# SCH_michale_nfc_2023-10-15.net
KiCad netlist of a schematic drawn in EasyEDA
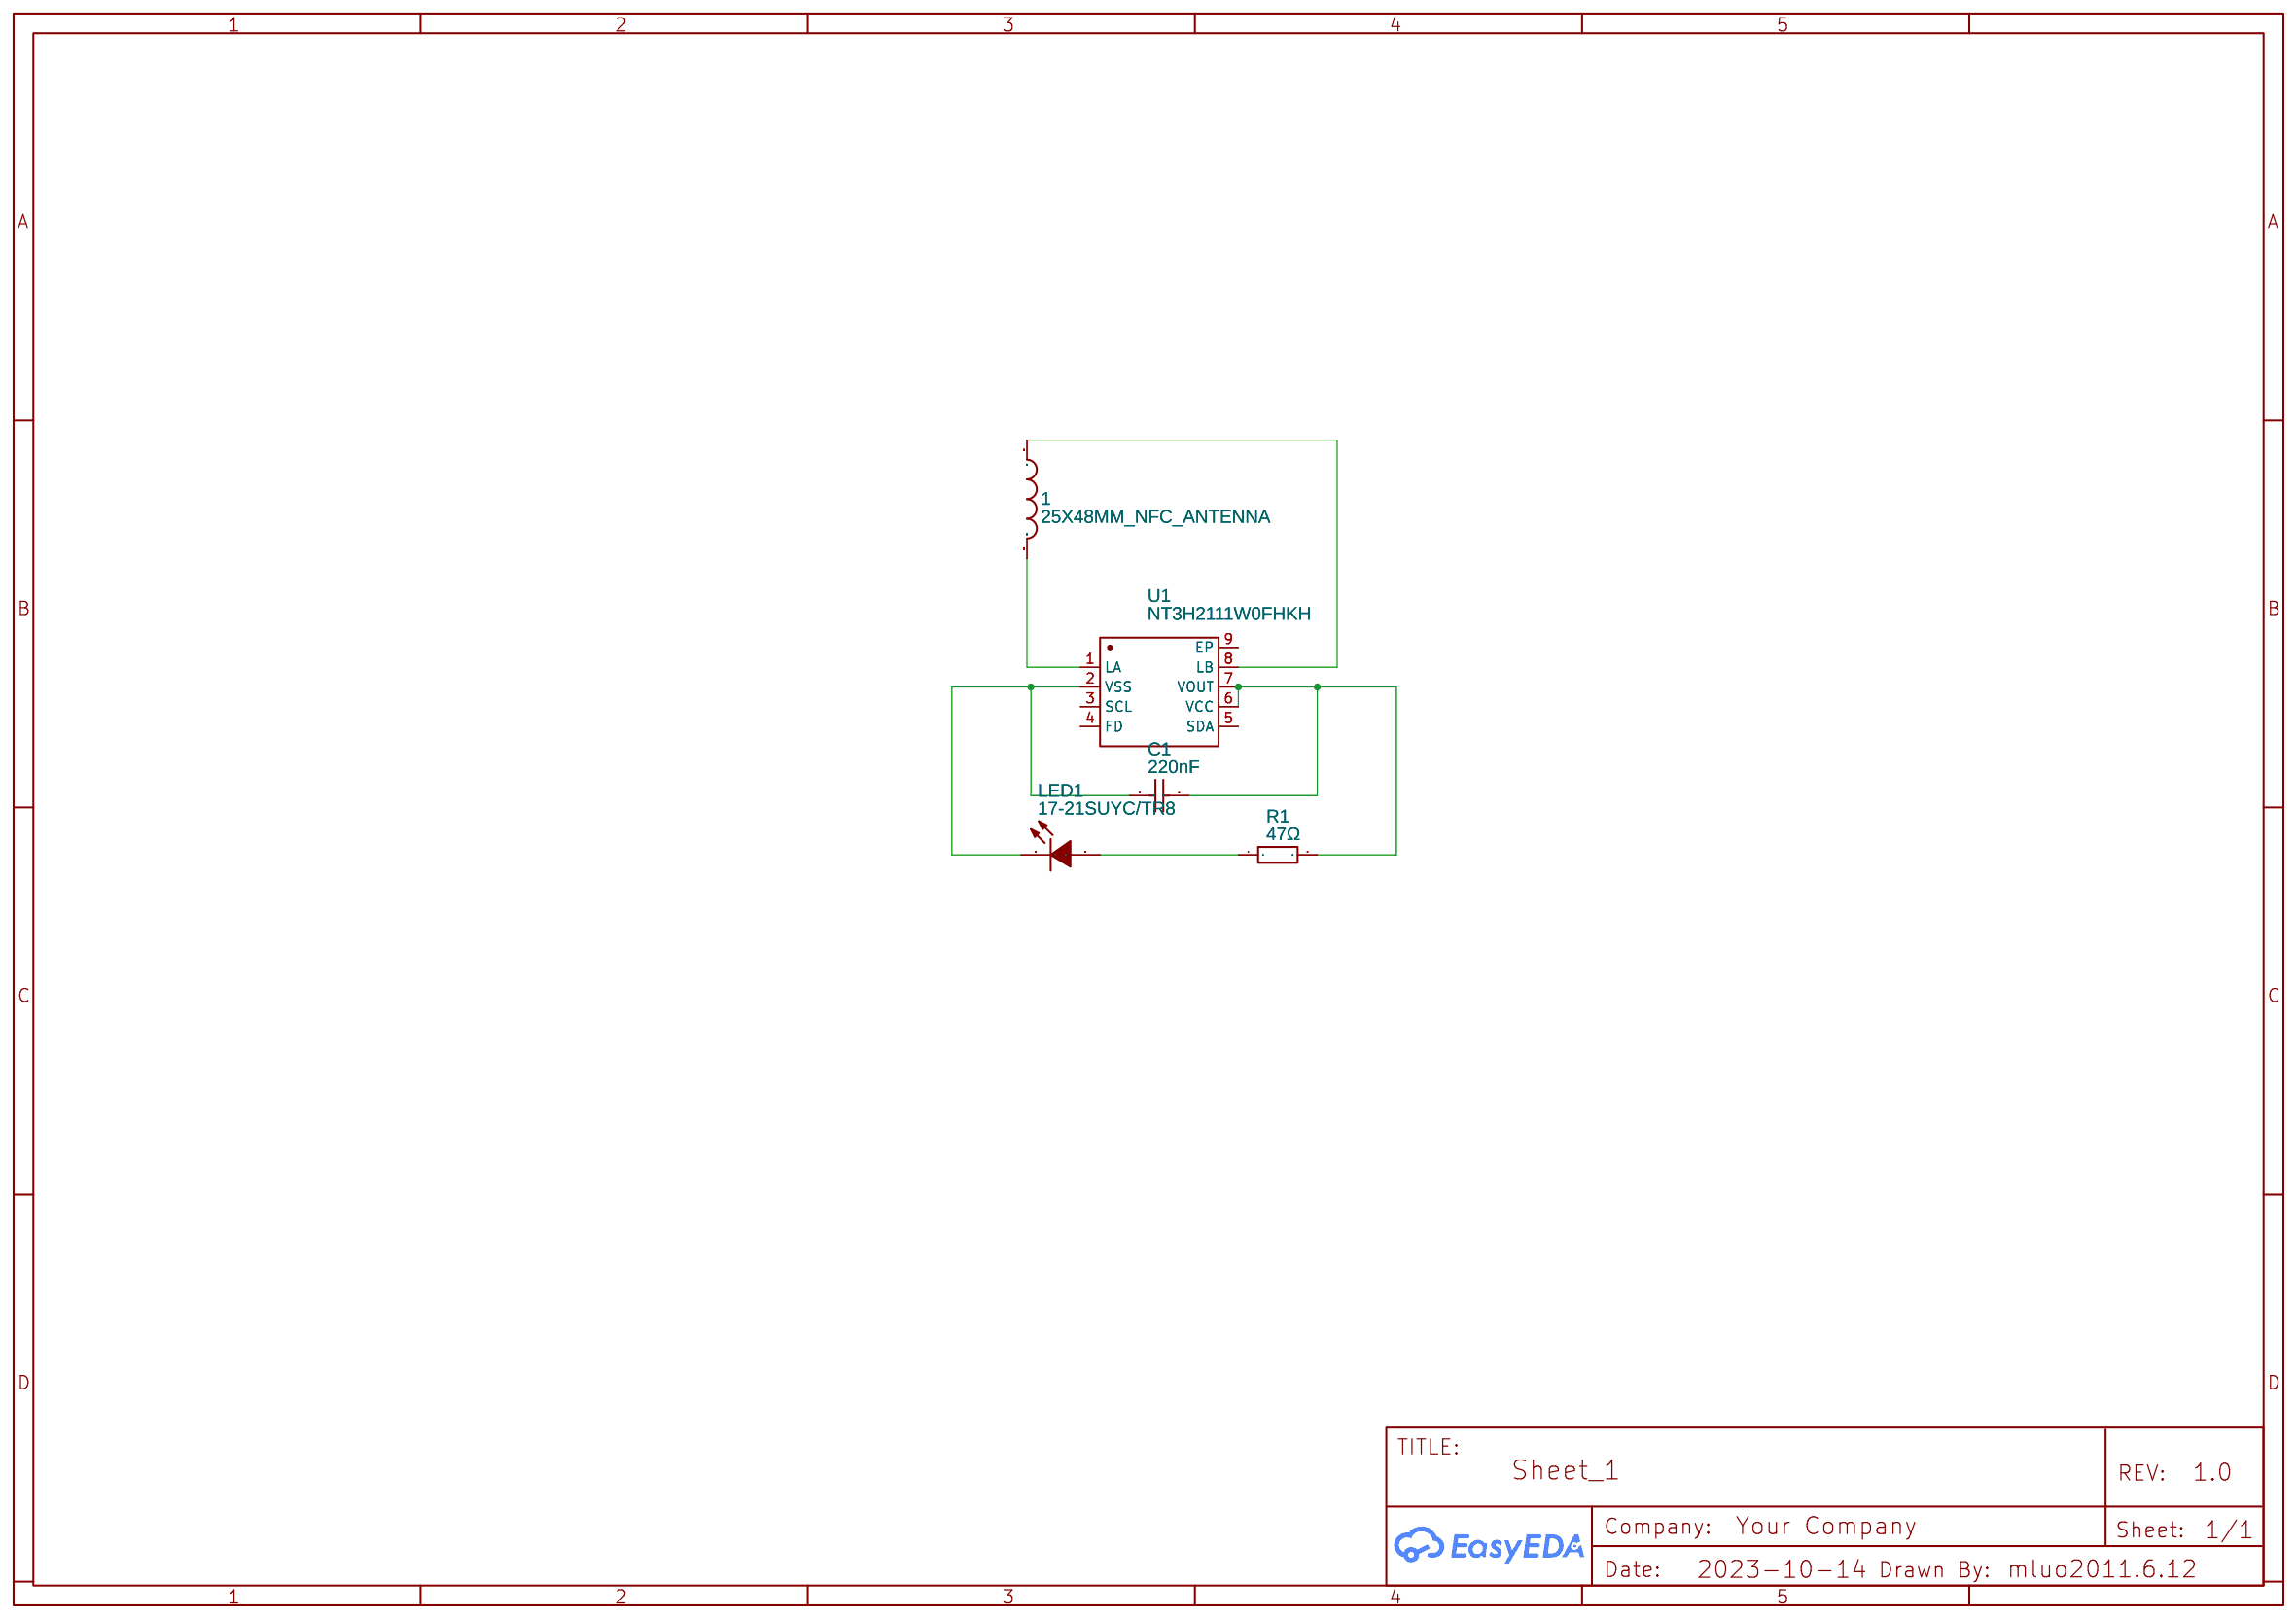
[diagram p0: schematic sheet]

(export (version "E")
  (design (tool "Eeschema 10.0.6"))
  (components
    (comp (ref "1") (value "25X48MM_NFC_ANTENNA") (libsource (lib "") (part "25X48MM_NFC_ANTENNA")))
    (comp (ref "C1")
      (value "220nF")
      (fields
        (field (name "Manufacturer Part") "CL10B224KA8NNNC")
        (field (name "Manufacturer") "SAMSUNG(三星)")
      )
      (libsource (lib "") (part "CL10B224KA8NNNC"))
    )
    (comp (ref "LED1")
      (value "17-21SUYC/TR8")
      (fields (field (name "Manufacturer Part") "KT-0805黄灯") (field (name "Manufacturer") "KENTO"))
      (libsource (lib "") (part "17-21SUYC/TR8"))
    )
    (comp (ref "R1")
      (value "47Ω")
      (fields
        (field (name "Manufacturer Part") "0603WAF470JT5E")
        (field (name "Manufacturer") "UNI-ROYAL(厚声)")
      )
      (libsource (lib "") (part "0603WAF470JT5E"))
    )
    (comp (ref "U1")
      (value "NT3H2111W0FHKH")
      (fields (field (name "Manufacturer") "NXP(恩智浦)"))
      (libsource (lib "") (part "NT3H2111W0FHKH"))
    )
  )
  (nets
    (net (code "1") (name "Net-(LED1-+)") (class "Default")
      (node (ref "LED1") (pin "1") (pinfunction "+_1") (pintype "unspecified"))
      (node (ref "R1") (pin "1") (pinfunction "1_1") (pintype "input"))
    )
    (net (code "2") (name "Net-(LED1--)") (class "Default")
      (node (ref "C1") (pin "1") (pinfunction "1_1") (pintype "input"))
      (node (ref "LED1") (pin "2") (pinfunction "-_2") (pintype "unspecified"))
      (node (ref "U1") (pin "2") (pinfunction "VSS_2") (pintype "unspecified"))
    )
    (net (code "3") (name "Net-(U1-LA)") (class "Default")
      (node (ref "1") (pin "P$2") (pinfunction "P$2_P$2") (pintype "bidirectional"))
      (node (ref "U1") (pin "1") (pinfunction "LA_1") (pintype "unspecified"))
    )
    (net (code "4") (name "Net-(U1-LB)") (class "Default")
      (node (ref "1") (pin "P$1") (pinfunction "P$1_P$1") (pintype "bidirectional"))
      (node (ref "U1") (pin "8") (pinfunction "LB_8") (pintype "unspecified"))
    )
    (net (code "5") (name "Net-(U1-VCC)") (class "Default")
      (node (ref "C1") (pin "2") (pinfunction "2_2") (pintype "input"))
      (node (ref "R1") (pin "2") (pinfunction "2_2") (pintype "input"))
      (node (ref "U1") (pin "6") (pinfunction "VCC_6") (pintype "unspecified"))
      (node (ref "U1") (pin "7") (pinfunction "VOUT_7") (pintype "unspecified"))
    )
    (net (code "6") (name "unconnected-(U1-EP-Pad9)") (class "Default")
      (node (ref "U1") (pin "9") (pinfunction "EP_9") (pintype "unspecified"))
    )
    (net (code "7") (name "unconnected-(U1-FD-Pad4)") (class "Default")
      (node (ref "U1") (pin "4") (pinfunction "FD_4") (pintype "unspecified"))
    )
    (net (code "8") (name "unconnected-(U1-SCL-Pad3)") (class "Default")
      (node (ref "U1") (pin "3") (pinfunction "SCL_3") (pintype "unspecified"))
    )
    (net (code "9") (name "unconnected-(U1-SDA-Pad5)") (class "Default")
      (node (ref "U1") (pin "5") (pinfunction "SDA_5") (pintype "unspecified"))
    )
  )
)
